# hothouse-switching-no-branding.net
KiCad netlist of a schematic drawn in EAGLE
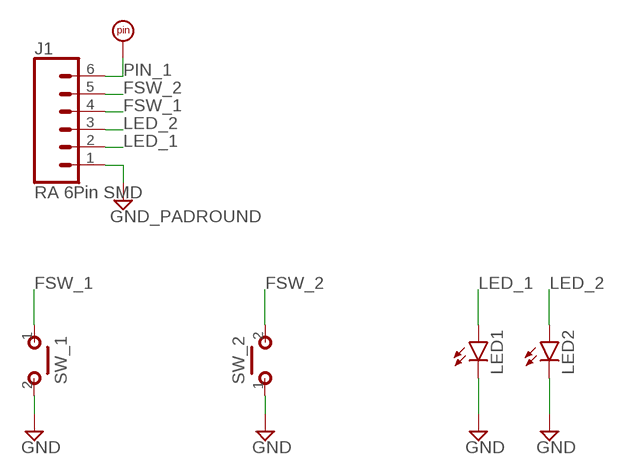
[diagram p0: schematic, sheet 1]

(export (version "E")
  (design (tool "Eeschema 10.0.6"))
  (components
    (comp (ref "GND2")
      (value "GND_PADROUND")
      (footprint "eagle-import:ROUND")
      (libsource (lib "eagle-import") (part "GND_PADROUND"))
    )
    (comp (ref "J1")
      (value "RA 6Pin SMD")
      (footprint "eagle-import:1X06")
      (libsource (lib "eagle-import") (part "CONN_06SILK_FEMALE_PTH"))
    )
    (comp (ref "LED1")
      (value "LED3MM")
      (footprint "eagle-import:LED3MM")
      (libsource (lib "eagle-import") (part "LED3MM"))
    )
    (comp (ref "LED2")
      (value "LED3MM")
      (footprint "eagle-import:LED3MM")
      (libsource (lib "eagle-import") (part "LED3MM"))
    )
    (comp (ref "SW_1")
      (value "SPST.PBS.MOM")
      (footprint "eagle-import:SPST.PBS.MOM")
      (libsource (lib "eagle-import") (part "SPST.PBS.MOM"))
    )
    (comp (ref "SW_2")
      (value "SPST.PBS.MOM")
      (footprint "eagle-import:SPST.PBS.MOM")
      (libsource (lib "eagle-import") (part "SPST.PBS.MOM"))
    )
    (comp (ref "U$5")
      (value "PADS.RND_NL")
      (footprint "eagle-import:PAD2")
      (libsource (lib "eagle-import") (part "PADS.RND_NL"))
    )
  )
  (nets
    (net (code "1") (name "/FSW_1") (class "Default")
      (node (ref "J1") (pin "4") (pinfunction "4_4") (pintype "passive"))
      (node (ref "SW_1") (pin "1") (pinfunction "P_1") (pintype "passive"))
    )
    (net (code "2") (name "/FSW_2") (class "Default")
      (node (ref "J1") (pin "5") (pinfunction "5_5") (pintype "passive"))
      (node (ref "SW_2") (pin "2") (pinfunction "S_2") (pintype "passive"))
    )
    (net (code "3") (name "/LED_1") (class "Default")
      (node (ref "J1") (pin "2") (pinfunction "2_2") (pintype "passive"))
      (node (ref "LED1") (pin "A") (pinfunction "A_A") (pintype "passive"))
    )
    (net (code "4") (name "/LED_2") (class "Default")
      (node (ref "J1") (pin "3") (pinfunction "3_3") (pintype "passive"))
      (node (ref "LED2") (pin "A") (pinfunction "A_A") (pintype "passive"))
    )
    (net (code "5") (name "/PIN_1") (class "Default")
      (node (ref "J1") (pin "6") (pinfunction "6_6") (pintype "passive"))
      (node (ref "U$5") (pin "P$1") (pinfunction "P$1_P$1") (pintype "bidirectional"))
    )
    (net (code "6") (name "GND") (class "Default")
      (node (ref "GND2") (pin "1") (pinfunction "GND_1") (pintype "power_in"))
      (node (ref "J1") (pin "1") (pinfunction "1_1") (pintype "passive"))
      (node (ref "LED1") (pin "K") (pinfunction "C_K") (pintype "passive"))
      (node (ref "LED2") (pin "K") (pinfunction "C_K") (pintype "passive"))
      (node (ref "SW_1") (pin "2") (pinfunction "S_2") (pintype "passive"))
      (node (ref "SW_2") (pin "1") (pinfunction "P_1") (pintype "passive"))
    )
  )
)
